# aafilter.net
KiCad netlist of a schematic drawn in Altium Designer
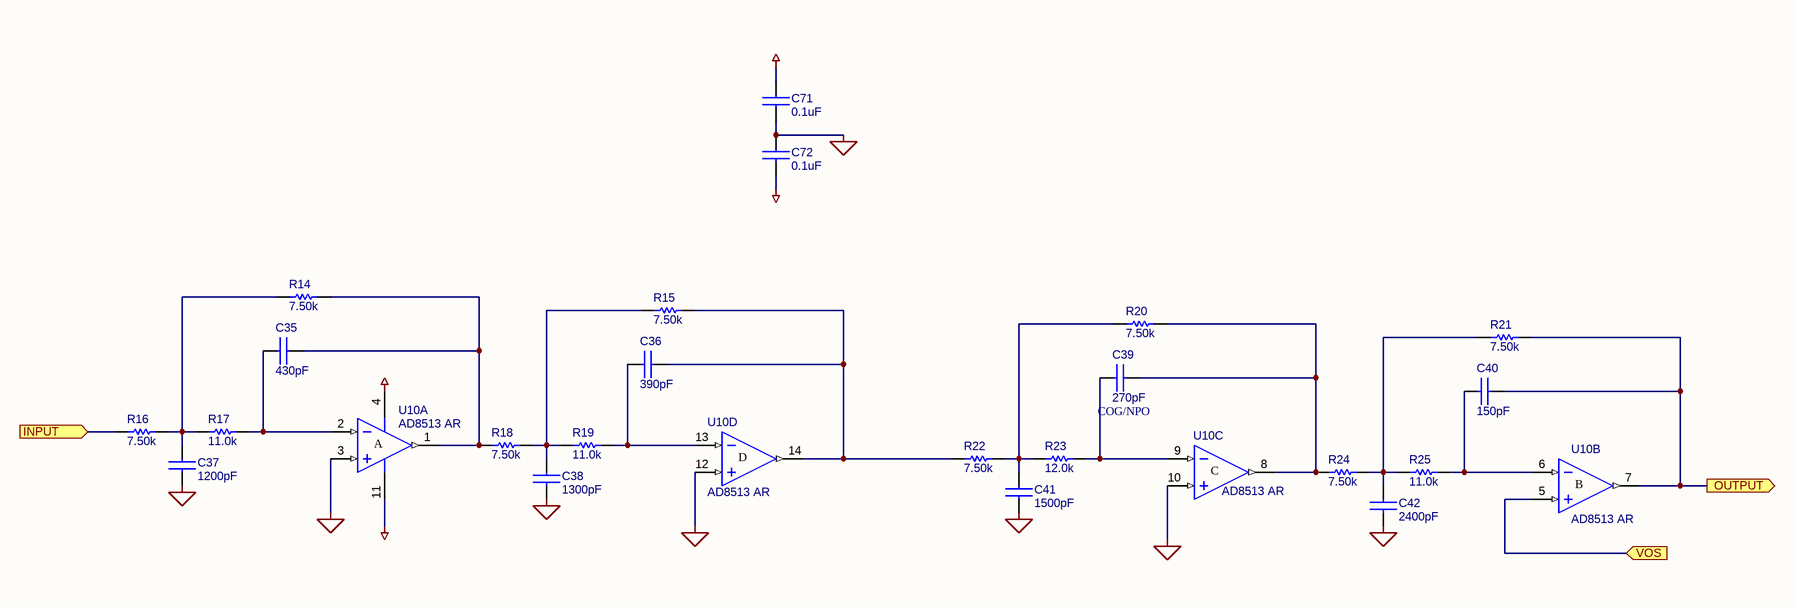
[diagram p0: aafilter.SCHDOC]

(export (version "E")
  (design (tool "Eeschema 10.0.6"))
  (components
    (comp (ref "C35")
      (value "430pF")
      (footprint "0603")
      (description "Standard Capacitor")
      (fields (field (name "Comment") "CAPACITOR"))
      (libsource (lib "parts") (part "CAPACITOR"))
    )
    (comp (ref "C36")
      (value "390pF")
      (footprint "0603")
      (description "Standard Capacitor")
      (fields (field (name "Comment") "CAPACITOR"))
      (libsource (lib "parts") (part "CAPACITOR"))
    )
    (comp (ref "C37")
      (value "1200pF")
      (footprint "0603")
      (description "Standard Capacitor")
      (fields (field (name "Comment") "CAPACITOR"))
      (libsource (lib "parts") (part "CAPACITOR"))
    )
    (comp (ref "C38")
      (value "1300pF")
      (footprint "0603")
      (description "Standard Capacitor")
      (fields (field (name "Comment") "CAPACITOR"))
      (libsource (lib "parts") (part "CAPACITOR"))
    )
    (comp (ref "C39")
      (value "270pF")
      (footprint "0603")
      (description "Standard Capacitor")
      (fields (field (name "TYPE") "COG/NPO") (field (name "Comment") "CAPACITOR"))
      (libsource (lib "parts") (part "CAPACITOR"))
    )
    (comp (ref "C40")
      (value "150pF")
      (footprint "0603")
      (description "Standard Capacitor")
      (fields (field (name "Comment") "CAPACITOR"))
      (libsource (lib "parts") (part "CAPACITOR"))
    )
    (comp (ref "C41")
      (value "1500pF")
      (footprint "0603")
      (description "Standard Capacitor")
      (fields (field (name "Comment") "CAPACITOR"))
      (libsource (lib "parts") (part "CAPACITOR"))
    )
    (comp (ref "C42")
      (value "2400pF")
      (footprint "0603")
      (description "Standard Capacitor")
      (fields (field (name "Comment") "CAPACITOR"))
      (libsource (lib "parts") (part "CAPACITOR"))
    )
    (comp (ref "C71")
      (value "0.1uF")
      (footprint "0603")
      (description "Standard Capacitor")
      (fields (field (name "Comment") "CAPACITOR"))
      (libsource (lib "parts") (part "CAPACITOR"))
    )
    (comp (ref "C72")
      (value "0.1uF")
      (footprint "0603")
      (description "Standard Capacitor")
      (fields (field (name "Comment") "CAPACITOR"))
      (libsource (lib "parts") (part "CAPACITOR"))
    )
    (comp (ref "R14")
      (value "7.50k")
      (footprint "0603")
      (description "Standard Passive Resistor")
      (fields (field (name "TOLERANCE") "1%") (field (name "Comment") "RESISTOR"))
      (libsource (lib "parts") (part "RESISTOR"))
    )
    (comp (ref "R15")
      (value "7.50k")
      (footprint "0603")
      (description "Standard Passive Resistor")
      (fields (field (name "TOLERANCE") "1%") (field (name "Comment") "RESISTOR"))
      (libsource (lib "parts") (part "RESISTOR"))
    )
    (comp (ref "R16")
      (value "7.50k")
      (footprint "0603")
      (description "Standard Passive Resistor")
      (fields (field (name "TOLERANCE") "1%") (field (name "Comment") "RESISTOR"))
      (libsource (lib "parts") (part "RESISTOR"))
    )
    (comp (ref "R17")
      (value "11.0k")
      (footprint "0603")
      (description "Standard Passive Resistor")
      (fields (field (name "TOLERANCE") "1%") (field (name "Comment") "RESISTOR"))
      (libsource (lib "parts") (part "RESISTOR"))
    )
    (comp (ref "R18")
      (value "7.50k")
      (footprint "0603")
      (description "Standard Passive Resistor")
      (fields (field (name "TOLERANCE") "1%") (field (name "Comment") "RESISTOR"))
      (libsource (lib "parts") (part "RESISTOR"))
    )
    (comp (ref "R19")
      (value "11.0k")
      (footprint "0603")
      (description "Standard Passive Resistor")
      (fields (field (name "TOLERANCE") "1%") (field (name "Comment") "RESISTOR"))
      (libsource (lib "parts") (part "RESISTOR"))
    )
    (comp (ref "R20")
      (value "7.50k")
      (footprint "0603")
      (description "Standard Passive Resistor")
      (fields (field (name "TOLERANCE") "1%") (field (name "Comment") "RESISTOR"))
      (libsource (lib "parts") (part "RESISTOR"))
    )
    (comp (ref "R21")
      (value "7.50k")
      (footprint "0603")
      (description "Standard Passive Resistor")
      (fields (field (name "TOLERANCE") "1%") (field (name "Comment") "RESISTOR"))
      (libsource (lib "parts") (part "RESISTOR"))
    )
    (comp (ref "R22")
      (value "7.50k")
      (footprint "0603")
      (description "Standard Passive Resistor")
      (fields (field (name "TOLERANCE") "1%") (field (name "Comment") "RESISTOR"))
      (libsource (lib "parts") (part "RESISTOR"))
    )
    (comp (ref "R23")
      (value "12.0k")
      (footprint "0603")
      (description "Standard Passive Resistor")
      (fields (field (name "TOLERANCE") "1%") (field (name "Comment") "RESISTOR"))
      (libsource (lib "parts") (part "RESISTOR"))
    )
    (comp (ref "R24")
      (value "7.50k")
      (footprint "0603")
      (description "Standard Passive Resistor")
      (fields (field (name "TOLERANCE") "1%") (field (name "Comment") "RESISTOR"))
      (libsource (lib "parts") (part "RESISTOR"))
    )
    (comp (ref "R25")
      (value "11.0k")
      (footprint "0603")
      (description "Standard Passive Resistor")
      (fields (field (name "TOLERANCE") "1%") (field (name "Comment") "RESISTOR"))
      (libsource (lib "parts") (part "RESISTOR"))
    )
    (comp (ref "U10")
      (value "AD8513 AR")
      (footprint "SO-G14")
      (description "low-noise JFET quad OA")
      (fields (field (name "PART") "AD8513AR"))
      (libsource (lib "parts") (part "AD8513ARU"))
    )
  )
  (nets
    (net (code "1") (name "/INPUT") (class "Default") (node (ref "R16") (pin "1") (pintype "passive")))
    (net (code "2") (name "/OUTPUT") (class "Default")
      (node (ref "C40") (pin "1") (pintype "passive"))
      (node (ref "R21") (pin "1") (pintype "passive"))
      (node (ref "U10") (pin "7") (pinfunction "OUTB_7") (pintype "output"))
    )
    (net (code "3") (name "/VOS") (class "Default")
      (node (ref "U10") (pin "5") (pinfunction "IN+B_5") (pintype "input"))
    )
    (net (code "4") (name "AGND") (class "Default")
      (node (ref "C37") (pin "1") (pintype "passive"))
      (node (ref "C38") (pin "1") (pintype "passive"))
      (node (ref "C41") (pin "1") (pintype "passive"))
      (node (ref "C42") (pin "1") (pintype "passive"))
      (node (ref "C71") (pin "1") (pintype "passive"))
      (node (ref "C72") (pin "2") (pintype "passive"))
      (node (ref "U10") (pin "10") (pinfunction "IN+C_10") (pintype "input"))
      (node (ref "U10") (pin "12") (pinfunction "IN+D_12") (pintype "input"))
      (node (ref "U10") (pin "3") (pinfunction "IN+A_3") (pintype "input"))
    )
    (net (code "5") (name "AVDD") (class "Default")
      (node (ref "C71") (pin "2") (pintype "passive"))
      (node (ref "U10") (pin "4") (pinfunction "V+_4") (pintype "power_in"))
    )
    (net (code "6") (name "AVSS") (class "Default")
      (node (ref "C72") (pin "1") (pintype "passive"))
      (node (ref "U10") (pin "11") (pinfunction "V-_11") (pintype "power_in"))
    )
    (net (code "7") (name "Net-(C37-Pad2)") (class "Default")
      (node (ref "C37") (pin "2") (pintype "passive"))
      (node (ref "R14") (pin "2") (pintype "passive"))
      (node (ref "R16") (pin "2") (pintype "passive"))
      (node (ref "R17") (pin "1") (pintype "passive"))
    )
    (net (code "8") (name "Net-(C38-Pad2)") (class "Default")
      (node (ref "C38") (pin "2") (pintype "passive"))
      (node (ref "R15") (pin "2") (pintype "passive"))
      (node (ref "R18") (pin "2") (pintype "passive"))
      (node (ref "R19") (pin "1") (pintype "passive"))
    )
    (net (code "9") (name "Net-(C41-Pad2)") (class "Default")
      (node (ref "C41") (pin "2") (pintype "passive"))
      (node (ref "R20") (pin "2") (pintype "passive"))
      (node (ref "R22") (pin "2") (pintype "passive"))
      (node (ref "R23") (pin "1") (pintype "passive"))
    )
    (net (code "10") (name "Net-(C42-Pad2)") (class "Default")
      (node (ref "C42") (pin "2") (pintype "passive"))
      (node (ref "R21") (pin "2") (pintype "passive"))
      (node (ref "R24") (pin "2") (pintype "passive"))
      (node (ref "R25") (pin "1") (pintype "passive"))
    )
    (net (code "11") (name "Net-(U10A-IN-A)") (class "Default")
      (node (ref "C35") (pin "2") (pintype "passive"))
      (node (ref "R17") (pin "2") (pintype "passive"))
      (node (ref "U10") (pin "2") (pinfunction "IN-A_2") (pintype "input"))
    )
    (net (code "12") (name "Net-(U10A-OUTA)") (class "Default")
      (node (ref "C35") (pin "1") (pintype "passive"))
      (node (ref "R14") (pin "1") (pintype "passive"))
      (node (ref "R18") (pin "1") (pintype "passive"))
      (node (ref "U10") (pin "1") (pinfunction "OUTA_1") (pintype "output"))
    )
    (net (code "13") (name "Net-(U10B-IN-B)") (class "Default")
      (node (ref "C40") (pin "2") (pintype "passive"))
      (node (ref "R25") (pin "2") (pintype "passive"))
      (node (ref "U10") (pin "6") (pinfunction "IN-B_6") (pintype "input"))
    )
    (net (code "14") (name "Net-(U10C-IN-C)") (class "Default")
      (node (ref "C39") (pin "2") (pintype "passive"))
      (node (ref "R23") (pin "2") (pintype "passive"))
      (node (ref "U10") (pin "9") (pinfunction "IN-C_9") (pintype "input"))
    )
    (net (code "15") (name "Net-(U10C-OUTC)") (class "Default")
      (node (ref "C39") (pin "1") (pintype "passive"))
      (node (ref "R20") (pin "1") (pintype "passive"))
      (node (ref "R24") (pin "1") (pintype "passive"))
      (node (ref "U10") (pin "8") (pinfunction "OUTC_8") (pintype "output"))
    )
    (net (code "16") (name "Net-(U10D-IN-D)") (class "Default")
      (node (ref "C36") (pin "2") (pintype "passive"))
      (node (ref "R19") (pin "2") (pintype "passive"))
      (node (ref "U10") (pin "13") (pinfunction "IN-D_13") (pintype "input"))
    )
    (net (code "17") (name "Net-(U10D-OUTD)") (class "Default")
      (node (ref "C36") (pin "1") (pintype "passive"))
      (node (ref "R15") (pin "1") (pintype "passive"))
      (node (ref "R22") (pin "1") (pintype "passive"))
      (node (ref "U10") (pin "14") (pinfunction "OUTD_14") (pintype "output"))
    )
  )
)
